# Ethernet.net
KiCad netlist of a schematic drawn in Altium Designer
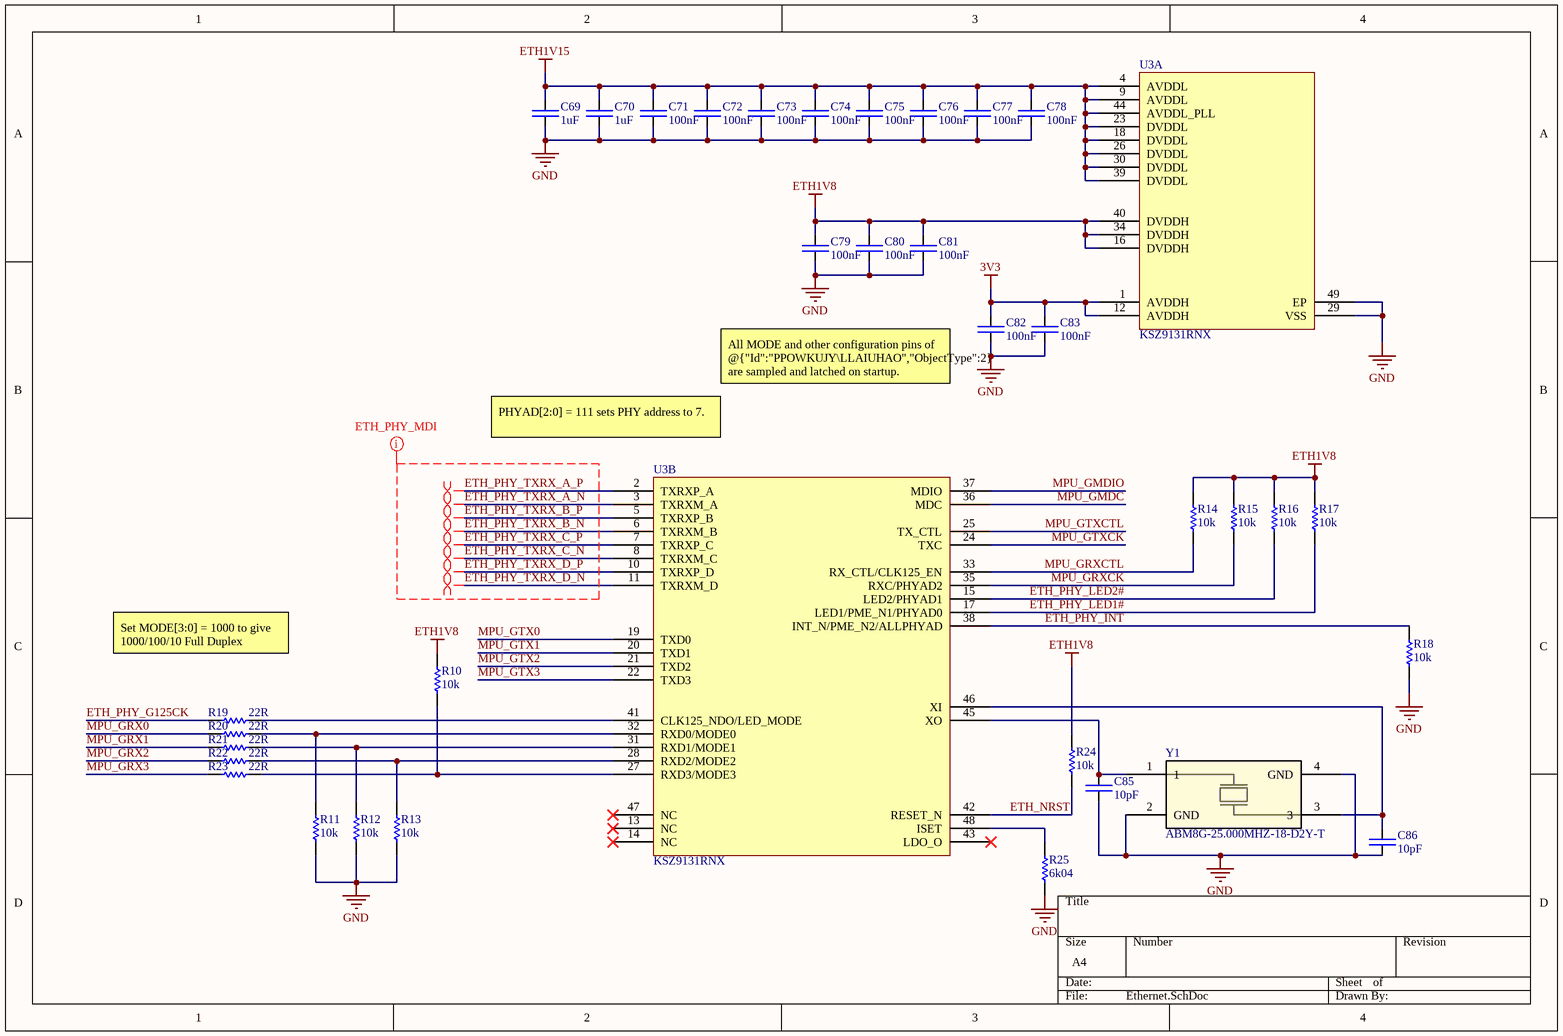
[diagram p0: Ethernet.SchDoc]

(export (version "E")
  (design (tool "Eeschema 10.0.6"))
  (components
    (comp (ref "C69")
      (value "1uF")
      (footprint "CAP-0805")
      (description "Capacitor chip unpolarized. 0805")
      (libsource (lib "Master") (part "CAP-0805"))
    )
    (comp (ref "C70")
      (value "1uF")
      (footprint "CAP-0805")
      (description "Capacitor chip unpolarized. 0805")
      (libsource (lib "Master") (part "CAP-0805"))
    )
    (comp (ref "C71")
      (value "100nF")
      (footprint "CAP-0603")
      (description "Capacitor chip unpolarized. 0603")
      (libsource (lib "Master") (part "CAP-0603"))
    )
    (comp (ref "C72")
      (value "100nF")
      (footprint "CAP-0603")
      (description "Capacitor chip unpolarized. 0603")
      (libsource (lib "Master") (part "CAP-0603"))
    )
    (comp (ref "C73")
      (value "100nF")
      (footprint "CAP-0603")
      (description "Capacitor chip unpolarized. 0603")
      (libsource (lib "Master") (part "CAP-0603"))
    )
    (comp (ref "C74")
      (value "100nF")
      (footprint "CAP-0603")
      (description "Capacitor chip unpolarized. 0603")
      (libsource (lib "Master") (part "CAP-0603"))
    )
    (comp (ref "C75")
      (value "100nF")
      (footprint "CAP-0603")
      (description "Capacitor chip unpolarized. 0603")
      (libsource (lib "Master") (part "CAP-0603"))
    )
    (comp (ref "C76")
      (value "100nF")
      (footprint "CAP-0603")
      (description "Capacitor chip unpolarized. 0603")
      (libsource (lib "Master") (part "CAP-0603"))
    )
    (comp (ref "C77")
      (value "100nF")
      (footprint "CAP-0603")
      (description "Capacitor chip unpolarized. 0603")
      (libsource (lib "Master") (part "CAP-0603"))
    )
    (comp (ref "C78")
      (value "100nF")
      (footprint "CAP-0603")
      (description "Capacitor chip unpolarized. 0603")
      (libsource (lib "Master") (part "CAP-0603"))
    )
    (comp (ref "C79")
      (value "100nF")
      (footprint "CAP-0603")
      (description "Capacitor chip unpolarized. 0603")
      (libsource (lib "Master") (part "CAP-0603"))
    )
    (comp (ref "C80")
      (value "100nF")
      (footprint "CAP-0603")
      (description "Capacitor chip unpolarized. 0603")
      (libsource (lib "Master") (part "CAP-0603"))
    )
    (comp (ref "C81")
      (value "100nF")
      (footprint "CAP-0603")
      (description "Capacitor chip unpolarized. 0603")
      (libsource (lib "Master") (part "CAP-0603"))
    )
    (comp (ref "C82")
      (value "100nF")
      (footprint "CAP-0603")
      (description "Capacitor chip unpolarized. 0603")
      (libsource (lib "Master") (part "CAP-0603"))
    )
    (comp (ref "C83")
      (value "100nF")
      (footprint "CAP-0603")
      (description "Capacitor chip unpolarized. 0603")
      (libsource (lib "Master") (part "CAP-0603"))
    )
    (comp (ref "C85")
      (value "10pF")
      (footprint "CAP-0603")
      (description "Capacitor chip unpolarized. 0603")
      (libsource (lib "Master") (part "CAP-0603"))
    )
    (comp (ref "C86")
      (value "10pF")
      (footprint "CAP-0603")
      (description "Capacitor chip unpolarized. 0603")
      (libsource (lib "Master") (part "CAP-0603"))
    )
    (comp (ref "R10")
      (value "10k")
      (footprint "RES-0603")
      (description "Resistor chip. 0603")
      (libsource (lib "Master") (part "RES-0603"))
    )
    (comp (ref "R11")
      (value "10k")
      (footprint "RES-0603")
      (description "Resistor chip. 0603")
      (libsource (lib "Master") (part "RES-0603"))
    )
    (comp (ref "R12")
      (value "10k")
      (footprint "RES-0603")
      (description "Resistor chip. 0603")
      (libsource (lib "Master") (part "RES-0603"))
    )
    (comp (ref "R13")
      (value "10k")
      (footprint "RES-0603")
      (description "Resistor chip. 0603")
      (libsource (lib "Master") (part "RES-0603"))
    )
    (comp (ref "R14")
      (value "10k")
      (footprint "RES-0603")
      (description "Resistor chip. 0603")
      (libsource (lib "Master") (part "RES-0603"))
    )
    (comp (ref "R15")
      (value "10k")
      (footprint "RES-0603")
      (description "Resistor chip. 0603")
      (libsource (lib "Master") (part "RES-0603"))
    )
    (comp (ref "R16")
      (value "10k")
      (footprint "RES-0603")
      (description "Resistor chip. 0603")
      (libsource (lib "Master") (part "RES-0603"))
    )
    (comp (ref "R17")
      (value "10k")
      (footprint "RES-0603")
      (description "Resistor chip. 0603")
      (libsource (lib "Master") (part "RES-0603"))
    )
    (comp (ref "R18")
      (value "10k")
      (footprint "RES-0603")
      (description "Resistor chip. 0603")
      (libsource (lib "Master") (part "RES-0603"))
    )
    (comp (ref "R19")
      (value "22R")
      (footprint "RES-0603")
      (description "Resistor chip. 0603")
      (libsource (lib "Master") (part "RES-0603"))
    )
    (comp (ref "R20")
      (value "22R")
      (footprint "RES-0603")
      (description "Resistor chip. 0603")
      (libsource (lib "Master") (part "RES-0603"))
    )
    (comp (ref "R21")
      (value "22R")
      (footprint "RES-0603")
      (description "Resistor chip. 0603")
      (libsource (lib "Master") (part "RES-0603"))
    )
    (comp (ref "R22")
      (value "22R")
      (footprint "RES-0603")
      (description "Resistor chip. 0603")
      (libsource (lib "Master") (part "RES-0603"))
    )
    (comp (ref "R23")
      (value "22R")
      (footprint "RES-0603")
      (description "Resistor chip. 0603")
      (libsource (lib "Master") (part "RES-0603"))
    )
    (comp (ref "R24")
      (value "10k")
      (footprint "RES-0603")
      (description "Resistor chip. 0603")
      (libsource (lib "Master") (part "RES-0603"))
    )
    (comp (ref "R25")
      (value "6k04")
      (footprint "RES-0603")
      (description "Resistor chip. 0603")
      (libsource (lib "Master") (part "RES-0603"))
    )
    (comp (ref "U3")
      (value "KSZ9131RNX")
      (footprint "KSZ9131RNXC-TR")
      (description "Eth PHY Gigabit")
      (libsource (lib "Master") (part "KSZ9131RNX"))
    )
    (comp (ref "Y1")
      (value "ABM8G-25.000MHZ-18-D2Y-T")
      (footprint "CRYSTAL_ABM8G_ABR")
      (description "Description")
      (fields (field (name "COPYRIGHT") "Copyright (C) 2026 Ultra Librarian. All rights reserved."))
      (libsource (lib "Master") (part "ABM8G-25.000MHZ-18-D2Y-T"))
    )
  )
  (nets
    (net (code "1") (name "/ETH_NRST") (class "Default")
      (node (ref "R24") (pin "1") (pintype "passive"))
      (node (ref "U3") (pin "42") (pinfunction "RESET_N_42") (pintype "passive"))
    )
    (net (code "2") (name "/ETH_PHY_G125CK") (class "Default")
      (node (ref "R19") (pin "2") (pintype "passive"))
    )
    (net (code "3") (name "/ETH_PHY_INT") (class "Default")
      (node (ref "R18") (pin "2") (pintype "passive"))
      (node (ref "U3") (pin "38") (pinfunction "INT_N/PME_N2/ALLPHYAD_38") (pintype "passive"))
    )
    (net (code "4") (name "/ETH_PHY_LED1#") (class "Default")
      (node (ref "R17") (pin "1") (pintype "passive"))
      (node (ref "U3") (pin "17") (pinfunction "LED1/PME_N1/PHYAD0_17") (pintype "passive"))
    )
    (net (code "5") (name "/ETH_PHY_LED2#") (class "Default")
      (node (ref "R16") (pin "1") (pintype "passive"))
      (node (ref "U3") (pin "15") (pinfunction "LED2/PHYAD1_15") (pintype "passive"))
    )
    (net (code "6") (name "/ETH_PHY_TXRX_A_N") (class "Default")
      (node (ref "U3") (pin "3") (pinfunction "TXRXM_A_3") (pintype "passive"))
    )
    (net (code "7") (name "/ETH_PHY_TXRX_A_P") (class "Default")
      (node (ref "U3") (pin "2") (pinfunction "TXRXP_A_2") (pintype "passive"))
    )
    (net (code "8") (name "/ETH_PHY_TXRX_B_N") (class "Default")
      (node (ref "U3") (pin "6") (pinfunction "TXRXM_B_6") (pintype "passive"))
    )
    (net (code "9") (name "/ETH_PHY_TXRX_B_P") (class "Default")
      (node (ref "U3") (pin "5") (pinfunction "TXRXP_B_5") (pintype "passive"))
    )
    (net (code "10") (name "/ETH_PHY_TXRX_C_N") (class "Default")
      (node (ref "U3") (pin "8") (pinfunction "TXRXM_C_8") (pintype "passive"))
    )
    (net (code "11") (name "/ETH_PHY_TXRX_C_P") (class "Default")
      (node (ref "U3") (pin "7") (pinfunction "TXRXP_C_7") (pintype "passive"))
    )
    (net (code "12") (name "/ETH_PHY_TXRX_D_N") (class "Default")
      (node (ref "U3") (pin "11") (pinfunction "TXRXM_D_11") (pintype "passive"))
    )
    (net (code "13") (name "/ETH_PHY_TXRX_D_P") (class "Default")
      (node (ref "U3") (pin "10") (pinfunction "TXRXP_D_10") (pintype "passive"))
    )
    (net (code "14") (name "/MPU_GMDC") (class "Default")
      (node (ref "U3") (pin "36") (pinfunction "MDC_36") (pintype "passive"))
    )
    (net (code "15") (name "/MPU_GMDIO") (class "Default")
      (node (ref "U3") (pin "37") (pinfunction "MDIO_37") (pintype "passive"))
    )
    (net (code "16") (name "/MPU_GRX0") (class "Default") (node (ref "R20") (pin "2") (pintype "passive")))
    (net (code "17") (name "/MPU_GRX1") (class "Default") (node (ref "R21") (pin "2") (pintype "passive")))
    (net (code "18") (name "/MPU_GRX2") (class "Default") (node (ref "R22") (pin "2") (pintype "passive")))
    (net (code "19") (name "/MPU_GRX3") (class "Default") (node (ref "R23") (pin "2") (pintype "passive")))
    (net (code "20") (name "/MPU_GRXCK") (class "Default")
      (node (ref "R15") (pin "1") (pintype "passive"))
      (node (ref "U3") (pin "35") (pinfunction "RXC/PHYAD2_35") (pintype "passive"))
    )
    (net (code "21") (name "/MPU_GRXCTL") (class "Default")
      (node (ref "R14") (pin "1") (pintype "passive"))
      (node (ref "U3") (pin "33") (pinfunction "RX_CTL/CLK125_EN_33") (pintype "passive"))
    )
    (net (code "22") (name "/MPU_GTX0") (class "Default")
      (node (ref "U3") (pin "19") (pinfunction "TXD0_19") (pintype "passive"))
    )
    (net (code "23") (name "/MPU_GTX1") (class "Default")
      (node (ref "U3") (pin "20") (pinfunction "TXD1_20") (pintype "passive"))
    )
    (net (code "24") (name "/MPU_GTX2") (class "Default")
      (node (ref "U3") (pin "21") (pinfunction "TXD2_21") (pintype "passive"))
    )
    (net (code "25") (name "/MPU_GTX3") (class "Default")
      (node (ref "U3") (pin "22") (pinfunction "TXD3_22") (pintype "passive"))
    )
    (net (code "26") (name "/MPU_GTXCK") (class "Default")
      (node (ref "U3") (pin "24") (pinfunction "TXC_24") (pintype "passive"))
    )
    (net (code "27") (name "/MPU_GTXCTL") (class "Default")
      (node (ref "U3") (pin "25") (pinfunction "TX_CTL_25") (pintype "passive"))
    )
    (net (code "28") (name "3V3") (class "Default")
      (node (ref "C82") (pin "2") (pintype "passive"))
      (node (ref "C83") (pin "2") (pintype "passive"))
      (node (ref "U3") (pin "1") (pinfunction "AVDDH_1") (pintype "passive"))
      (node (ref "U3") (pin "12") (pinfunction "AVDDH_12") (pintype "passive"))
    )
    (net (code "29") (name "ETH1V8") (class "Default")
      (node (ref "C79") (pin "2") (pintype "passive"))
      (node (ref "C80") (pin "2") (pintype "passive"))
      (node (ref "C81") (pin "2") (pintype "passive"))
      (node (ref "R10") (pin "2") (pintype "passive"))
      (node (ref "R14") (pin "2") (pintype "passive"))
      (node (ref "R15") (pin "2") (pintype "passive"))
      (node (ref "R16") (pin "2") (pintype "passive"))
      (node (ref "R17") (pin "2") (pintype "passive"))
      (node (ref "R24") (pin "2") (pintype "passive"))
      (node (ref "U3") (pin "16") (pinfunction "DVDDH_16") (pintype "passive"))
      (node (ref "U3") (pin "34") (pinfunction "DVDDH_34") (pintype "passive"))
      (node (ref "U3") (pin "40") (pinfunction "DVDDH_40") (pintype "passive"))
    )
    (net (code "30") (name "ETH1V15") (class "Default")
      (node (ref "C69") (pin "2") (pintype "passive"))
      (node (ref "C70") (pin "2") (pintype "passive"))
      (node (ref "C71") (pin "2") (pintype "passive"))
      (node (ref "C72") (pin "2") (pintype "passive"))
      (node (ref "C73") (pin "2") (pintype "passive"))
      (node (ref "C74") (pin "2") (pintype "passive"))
      (node (ref "C75") (pin "2") (pintype "passive"))
      (node (ref "C76") (pin "2") (pintype "passive"))
      (node (ref "C77") (pin "2") (pintype "passive"))
      (node (ref "C78") (pin "2") (pintype "passive"))
      (node (ref "U3") (pin "18") (pinfunction "DVDDL_18") (pintype "passive"))
      (node (ref "U3") (pin "23") (pinfunction "DVDDL_23") (pintype "passive"))
      (node (ref "U3") (pin "26") (pinfunction "DVDDL_26") (pintype "passive"))
      (node (ref "U3") (pin "30") (pinfunction "DVDDL_30") (pintype "passive"))
      (node (ref "U3") (pin "39") (pinfunction "DVDDL_39") (pintype "passive"))
      (node (ref "U3") (pin "4") (pinfunction "AVDDL_4") (pintype "passive"))
      (node (ref "U3") (pin "44") (pinfunction "AVDDL_PLL_44") (pintype "passive"))
      (node (ref "U3") (pin "9") (pinfunction "AVDDL_9") (pintype "passive"))
    )
    (net (code "31") (name "GND") (class "Default")
      (node (ref "C69") (pin "1") (pintype "passive"))
      (node (ref "C70") (pin "1") (pintype "passive"))
      (node (ref "C71") (pin "1") (pintype "passive"))
      (node (ref "C72") (pin "1") (pintype "passive"))
      (node (ref "C73") (pin "1") (pintype "passive"))
      (node (ref "C74") (pin "1") (pintype "passive"))
      (node (ref "C75") (pin "1") (pintype "passive"))
      (node (ref "C76") (pin "1") (pintype "passive"))
      (node (ref "C77") (pin "1") (pintype "passive"))
      (node (ref "C78") (pin "1") (pintype "passive"))
      (node (ref "C79") (pin "1") (pintype "passive"))
      (node (ref "C80") (pin "1") (pintype "passive"))
      (node (ref "C81") (pin "1") (pintype "passive"))
      (node (ref "C82") (pin "1") (pintype "passive"))
      (node (ref "C83") (pin "1") (pintype "passive"))
      (node (ref "C85") (pin "1") (pintype "passive"))
      (node (ref "C86") (pin "1") (pintype "passive"))
      (node (ref "R11") (pin "1") (pintype "passive"))
      (node (ref "R12") (pin "1") (pintype "passive"))
      (node (ref "R13") (pin "1") (pintype "passive"))
      (node (ref "R18") (pin "1") (pintype "passive"))
      (node (ref "R25") (pin "1") (pintype "passive"))
      (node (ref "U3") (pin "29") (pinfunction "VSS_29") (pintype "passive"))
      (node (ref "U3") (pin "49") (pinfunction "EP_49") (pintype "passive"))
      (node (ref "Y1") (pin "2") (pinfunction "GND_2") (pintype "passive"))
      (node (ref "Y1") (pin "4") (pinfunction "GND_4") (pintype "passive"))
    )
    (net (code "32") (name "Net-(U3B-CLK125_NDO{slash}LED_MODE)") (class "Default")
      (node (ref "R19") (pin "1") (pintype "passive"))
      (node (ref "U3") (pin "41") (pinfunction "CLK125_NDO/LED_MODE_41") (pintype "passive"))
    )
    (net (code "33") (name "Net-(U3B-ISET)") (class "Default")
      (node (ref "R25") (pin "2") (pintype "passive"))
      (node (ref "U3") (pin "48") (pinfunction "ISET_48") (pintype "passive"))
    )
    (net (code "34") (name "Net-(U3B-RXD0{slash}MODE0)") (class "Default")
      (node (ref "R11") (pin "2") (pintype "passive"))
      (node (ref "R20") (pin "1") (pintype "passive"))
      (node (ref "U3") (pin "32") (pinfunction "RXD0/MODE0_32") (pintype "passive"))
    )
    (net (code "35") (name "Net-(U3B-RXD1{slash}MODE1)") (class "Default")
      (node (ref "R12") (pin "2") (pintype "passive"))
      (node (ref "R21") (pin "1") (pintype "passive"))
      (node (ref "U3") (pin "31") (pinfunction "RXD1/MODE1_31") (pintype "passive"))
    )
    (net (code "36") (name "Net-(U3B-RXD2{slash}MODE2)") (class "Default")
      (node (ref "R13") (pin "2") (pintype "passive"))
      (node (ref "R22") (pin "1") (pintype "passive"))
      (node (ref "U3") (pin "28") (pinfunction "RXD2/MODE2_28") (pintype "passive"))
    )
    (net (code "37") (name "Net-(U3B-RXD3{slash}MODE3)") (class "Default")
      (node (ref "R10") (pin "1") (pintype "passive"))
      (node (ref "R23") (pin "1") (pintype "passive"))
      (node (ref "U3") (pin "27") (pinfunction "RXD3/MODE3_27") (pintype "passive"))
    )
    (net (code "38") (name "Net-(U3B-XI)") (class "Default")
      (node (ref "C86") (pin "2") (pintype "passive"))
      (node (ref "U3") (pin "46") (pinfunction "XI_46") (pintype "passive"))
      (node (ref "Y1") (pin "3") (pinfunction "3_3") (pintype "passive"))
    )
    (net (code "39") (name "Net-(U3B-XO)") (class "Default")
      (node (ref "C85") (pin "2") (pintype "passive"))
      (node (ref "U3") (pin "45") (pinfunction "XO_45") (pintype "passive"))
      (node (ref "Y1") (pin "1") (pinfunction "1_1") (pintype "passive"))
    )
    (net (code "40") (name "unconnected-(U3B-LDO_O-Pad43)") (class "Default")
      (node (ref "U3") (pin "43") (pinfunction "LDO_O_43") (pintype "passive+no_connect"))
    )
    (net (code "41") (name "unconnected-(U3B-NC-Pad13)") (class "Default")
      (node (ref "U3") (pin "13") (pinfunction "NC_13") (pintype "passive+no_connect"))
    )
    (net (code "42") (name "unconnected-(U3B-NC-Pad14)") (class "Default")
      (node (ref "U3") (pin "14") (pinfunction "NC_14") (pintype "passive+no_connect"))
    )
    (net (code "43") (name "unconnected-(U3B-NC-Pad47)") (class "Default")
      (node (ref "U3") (pin "47") (pinfunction "NC_47") (pintype "passive+no_connect"))
    )
  )
)
